# Arduino_Eth08d_MU-REV3.net
KiCad netlist of a schematic drawn in EAGLE
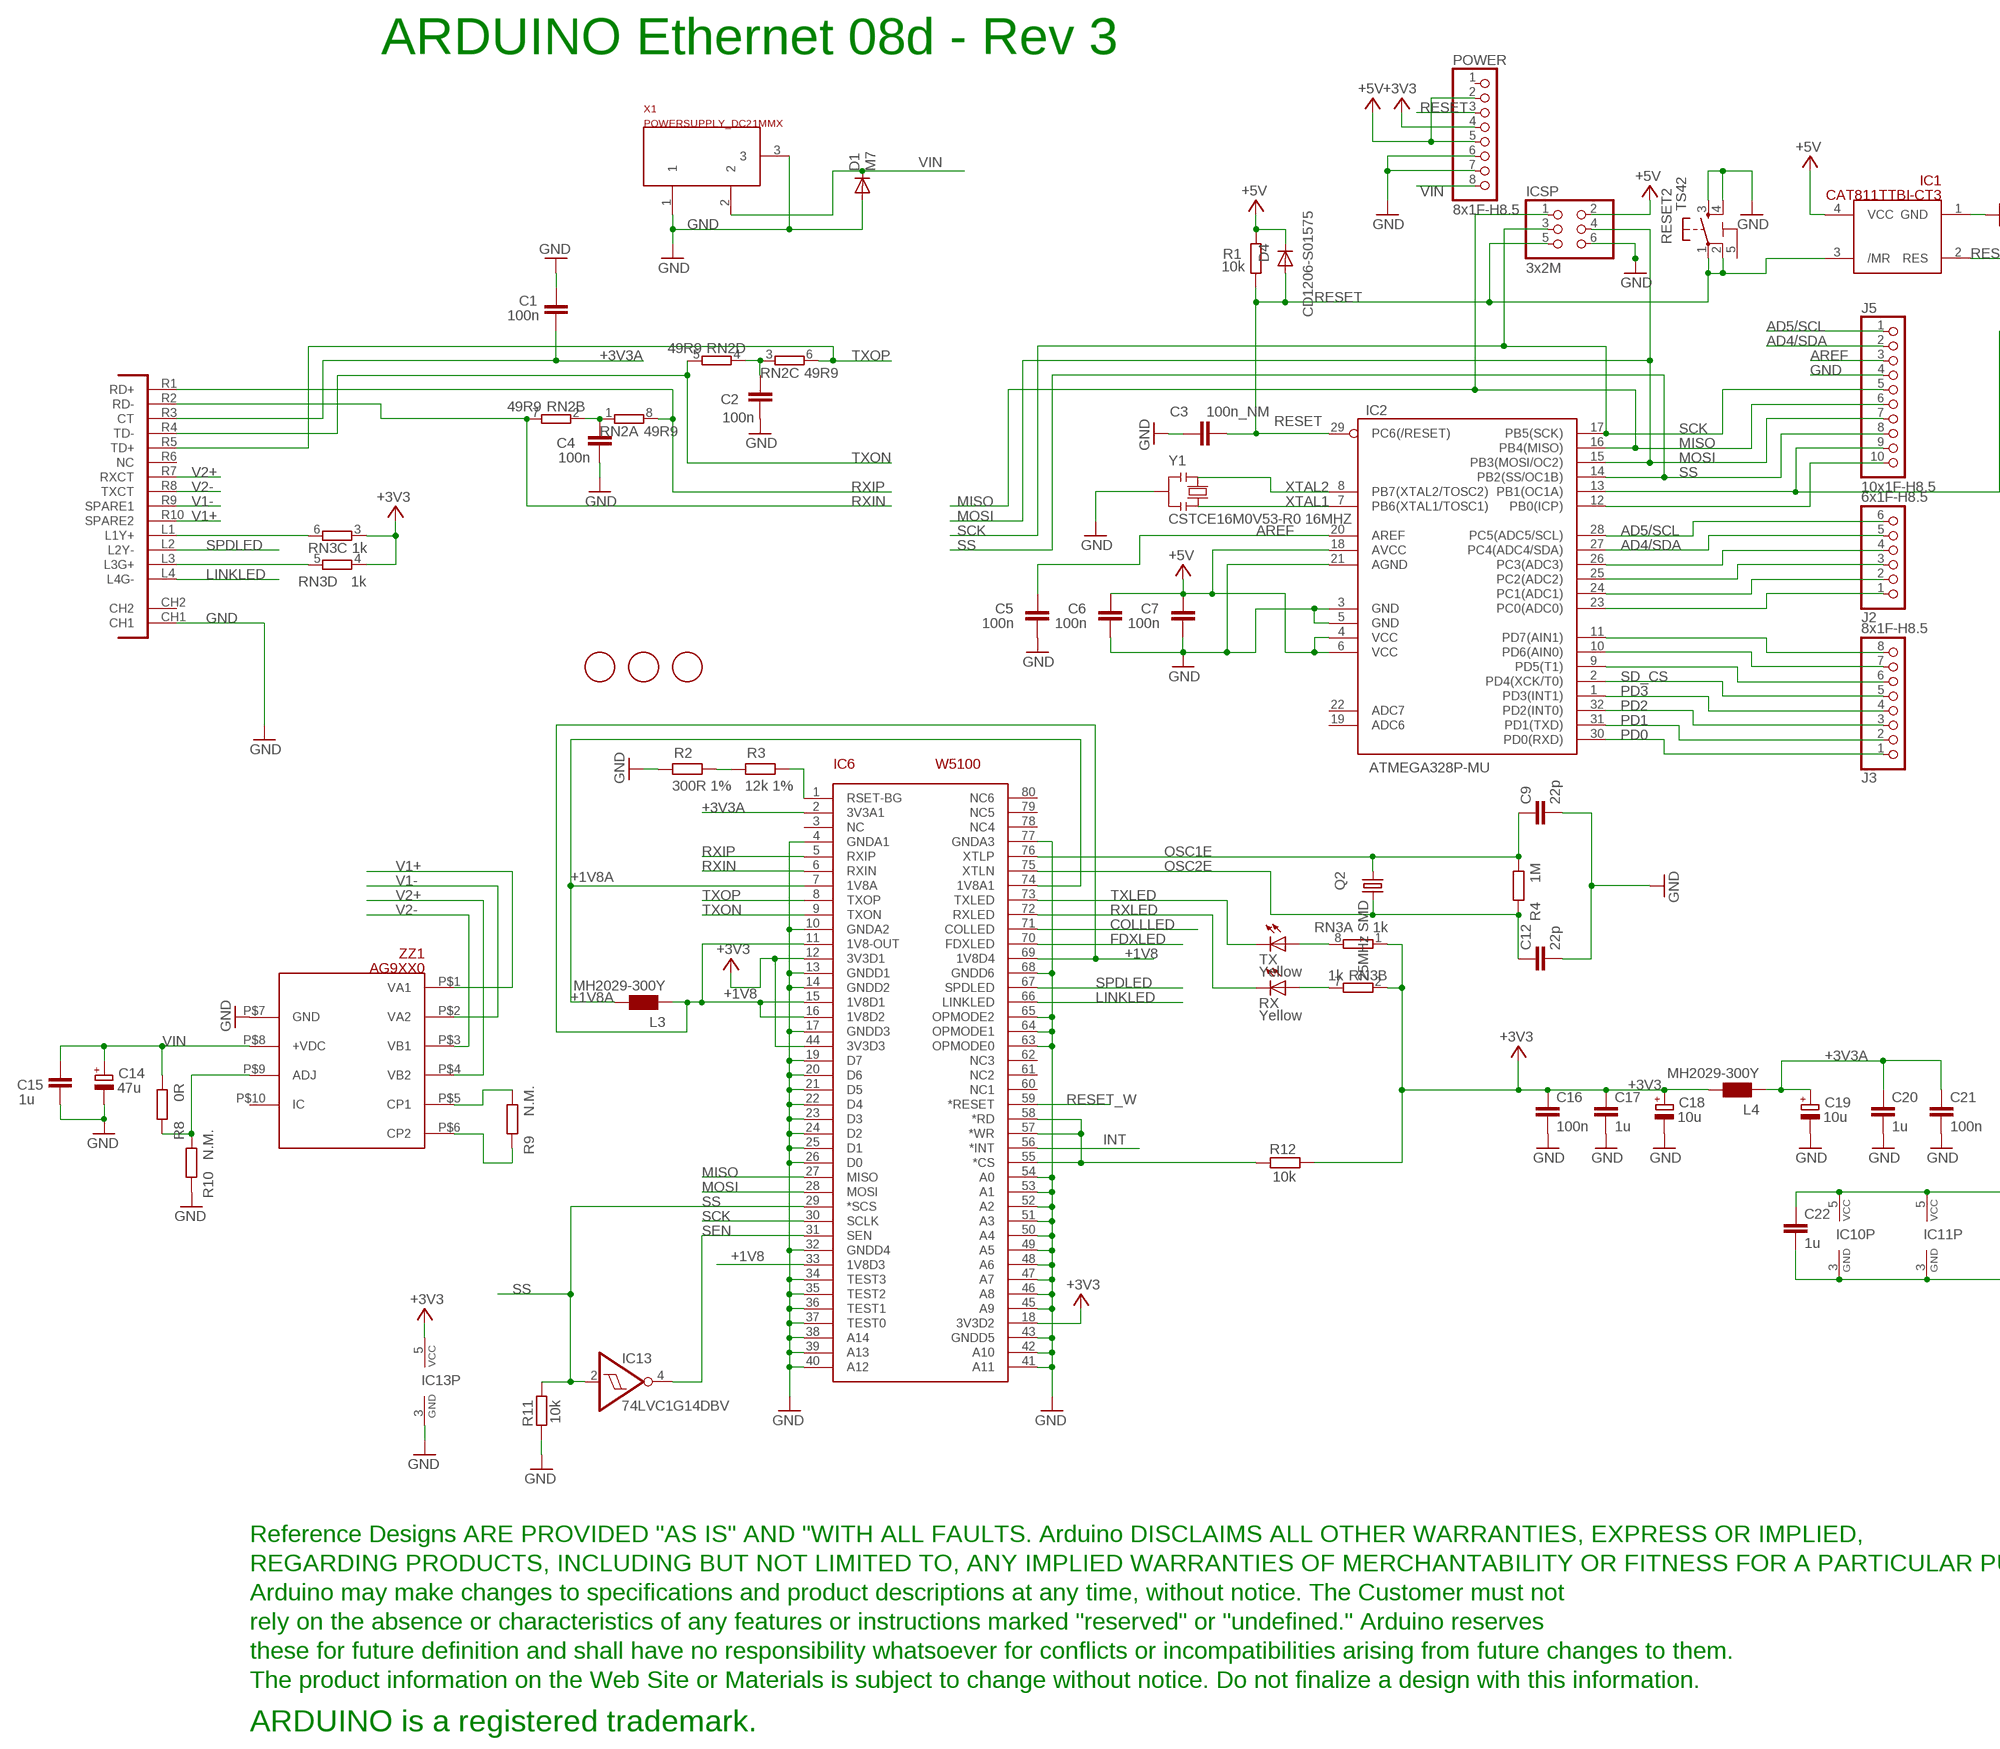
[diagram p0: schematic, sheet 1, part 1 of 2]
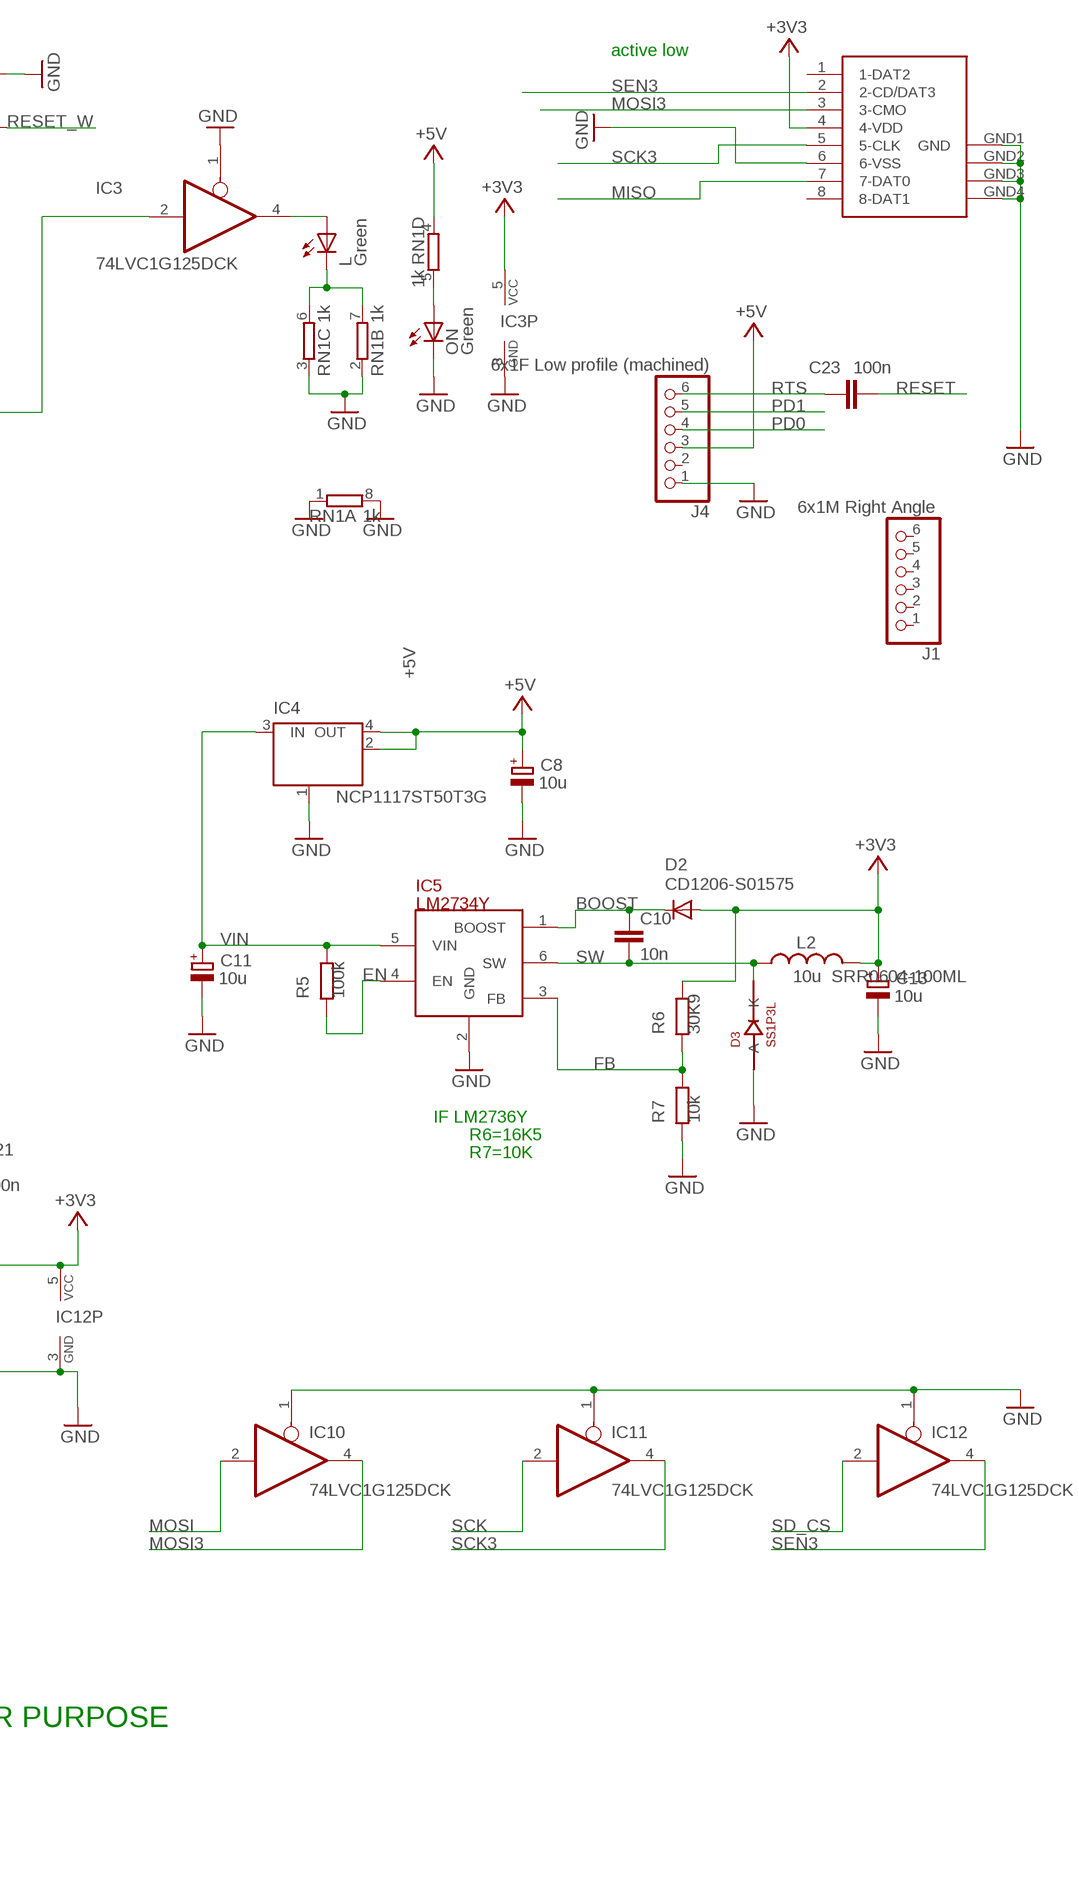
[diagram p1: schematic, sheet 1, part 2 of 2]

(export (version "E")
  (design (tool "Eeschema 10.0.6"))
  (components
    (comp (ref "C1")
      (value "100n")
      (footprint "eagle-import:C0603-ROUND")
      (libsource (lib "eagle-import") (part "C-EUC0603"))
    )
    (comp (ref "C2")
      (value "100n")
      (footprint "eagle-import:C0603-ROUND")
      (libsource (lib "eagle-import") (part "C-EUC0603"))
    )
    (comp (ref "C3")
      (value "100n_NM")
      (footprint "eagle-import:C0603-ROUND")
      (libsource (lib "eagle-import") (part "C-EUC0603"))
    )
    (comp (ref "C4")
      (value "100n")
      (footprint "eagle-import:C0603-ROUND")
      (libsource (lib "eagle-import") (part "C-EUC0603"))
    )
    (comp (ref "C5")
      (value "100n")
      (footprint "eagle-import:C0603-ROUND")
      (libsource (lib "eagle-import") (part "C-EUC0603"))
    )
    (comp (ref "C6")
      (value "100n")
      (footprint "eagle-import:C0603-ROUND")
      (libsource (lib "eagle-import") (part "C-EUC0603"))
    )
    (comp (ref "C7")
      (value "100n")
      (footprint "eagle-import:C0603-ROUND")
      (libsource (lib "eagle-import") (part "C-EUC0603"))
    )
    (comp (ref "C8")
      (value "10u")
      (footprint "eagle-import:SMC_B")
      (libsource (lib "eagle-import") (part "CPOL-EUSMCB"))
    )
    (comp (ref "C9")
      (value "22p")
      (footprint "eagle-import:C0603-ROUND")
      (libsource (lib "eagle-import") (part "C-EUC0603"))
    )
    (comp (ref "C10")
      (value "10n")
      (footprint "eagle-import:C0603-ROUND")
      (libsource (lib "eagle-import") (part "C-EUC0603"))
    )
    (comp (ref "C11")
      (value "10u")
      (footprint "eagle-import:SMC_B")
      (libsource (lib "eagle-import") (part "CPOL-EUSMCB"))
    )
    (comp (ref "C12")
      (value "22p")
      (footprint "eagle-import:C0603-ROUND")
      (libsource (lib "eagle-import") (part "C-EUC0603"))
    )
    (comp (ref "C13")
      (value "10u")
      (footprint "eagle-import:SMC_B")
      (libsource (lib "eagle-import") (part "CPOL-EUSMCB"))
    )
    (comp (ref "C14")
      (value "47u")
      (footprint "eagle-import:PANASONIC_D")
      (libsource (lib "eagle-import") (part "CPOL-EUD"))
    )
    (comp (ref "C15")
      (value "1u")
      (footprint "eagle-import:C0603-ROUND")
      (libsource (lib "eagle-import") (part "C-EUC0603"))
    )
    (comp (ref "C16")
      (value "100n")
      (footprint "eagle-import:C0603-ROUND")
      (libsource (lib "eagle-import") (part "C-EUC0603"))
    )
    (comp (ref "C17")
      (value "1u")
      (footprint "eagle-import:C0603-ROUND")
      (libsource (lib "eagle-import") (part "C-EUC0603"))
    )
    (comp (ref "C18")
      (value "10u")
      (footprint "eagle-import:SMC_B")
      (libsource (lib "eagle-import") (part "CPOL-EUSMCB"))
    )
    (comp (ref "C19")
      (value "10u")
      (footprint "eagle-import:SMC_B")
      (libsource (lib "eagle-import") (part "CPOL-EUSMCB"))
    )
    (comp (ref "C20")
      (value "1u")
      (footprint "eagle-import:C0603-ROUND")
      (libsource (lib "eagle-import") (part "C-EUC0603"))
    )
    (comp (ref "C21")
      (value "100n")
      (footprint "eagle-import:C0603-ROUND")
      (libsource (lib "eagle-import") (part "C-EUC0603"))
    )
    (comp (ref "C22")
      (value "1u")
      (footprint "eagle-import:C0603-ROUND")
      (libsource (lib "eagle-import") (part "C-EUC0603"))
    )
    (comp (ref "C23")
      (value "100n")
      (footprint "eagle-import:C0603-ROUND")
      (libsource (lib "eagle-import") (part "C-EUC0603"))
    )
    (comp (ref "D1")
      (value "M7")
      (footprint "eagle-import:SMB")
      (libsource (lib "eagle-import") (part "DIODE-SMB"))
    )
    (comp (ref "D2")
      (value "CD1206-S01575")
      (footprint "eagle-import:MINIMELF")
      (libsource (lib "eagle-import") (part "DIODE-MINIMELF"))
    )
    (comp (ref "D3")
      (value "SS1P3L")
      (footprint "eagle-import:DO220AAL")
      (libsource (lib "eagle-import") (part "SS1P3L"))
    )
    (comp (ref "D4")
      (value "CD1206-S01575")
      (footprint "eagle-import:MINIMELF")
      (libsource (lib "eagle-import") (part "DIODE-MINIMELF"))
    )
    (comp (ref "FD1")
      (value "FIDUCIALMOUNT")
      (footprint "eagle-import:FIDUCIA-MOUNT")
      (libsource (lib "eagle-import") (part "FIDUCIALMOUNT"))
    )
    (comp (ref "FD2")
      (value "FIDUCIALMOUNT")
      (footprint "eagle-import:FIDUCIA-MOUNT")
      (libsource (lib "eagle-import") (part "FIDUCIALMOUNT"))
    )
    (comp (ref "FD3")
      (value "FIDUCIALMOUNT")
      (footprint "eagle-import:FIDUCIA-MOUNT")
      (libsource (lib "eagle-import") (part "FIDUCIALMOUNT"))
    )
    (comp (ref "IC1")
      (value "CAT811TTBI-CT3")
      (footprint "eagle-import:SOT143")
      (libsource (lib "eagle-import") (part "STM812"))
    )
    (comp (ref "IC2")
      (value "ATMEGA328P-MU")
      (footprint "eagle-import:MLF32")
      (libsource (lib "eagle-import") (part "ATMEGAXX8-MUR"))
    )
    (comp (ref "IC3")
      (value "74LVC1G125DCK")
      (footprint "eagle-import:SC70-5")
      (libsource (lib "eagle-import") (part "741G125DCKLVC"))
    )
    (comp (ref "IC4")
      (value "NCP1117ST50T3G")
      (footprint "eagle-import:LINEAR_SOT223")
      (libsource (lib "eagle-import") (part "LINEAR_MC33269ST"))
    )
    (comp (ref "IC5")
      (value "LM2734Y")
      (footprint "eagle-import:SOT23-6")
      (libsource (lib "eagle-import") (part "LM2736Y"))
    )
    (comp (ref "IC6")
      (value "W5100")
      (footprint "eagle-import:SQFP-S-10X10-80")
      (libsource (lib "eagle-import") (part "W5100"))
    )
    (comp (ref "IC10")
      (value "74LVC1G125DCK")
      (footprint "eagle-import:SC70-5")
      (libsource (lib "eagle-import") (part "741G125DCKLVC"))
    )
    (comp (ref "IC11")
      (value "74LVC1G125DCK")
      (footprint "eagle-import:SC70-5")
      (libsource (lib "eagle-import") (part "741G125DCKLVC"))
    )
    (comp (ref "IC12")
      (value "74LVC1G125DCK")
      (footprint "eagle-import:SC70-5")
      (libsource (lib "eagle-import") (part "741G125DCKLVC"))
    )
    (comp (ref "IC13")
      (value "74LVC1G14DBV")
      (footprint "eagle-import:SOT23-5")
      (libsource (lib "eagle-import") (part "741G14DBVLVC"))
    )
    (comp (ref "ICSP")
      (value "3x2M")
      (footprint "eagle-import:2X03")
      (libsource (lib "eagle-import") (part "PINHD-2X3"))
    )
    (comp (ref "J1")
      (value "6x1M Right Angle")
      (footprint "eagle-import:1X06_90")
      (libsource (lib "eagle-import") (part "PINHD-1X6/90"))
    )
    (comp (ref "J2")
      (value "6x1F-H8.5")
      (footprint "eagle-import:1X06")
      (libsource (lib "eagle-import") (part "PINHD-1X6"))
    )
    (comp (ref "J3")
      (value "8x1F-H8.5")
      (footprint "eagle-import:1X08")
      (libsource (lib "eagle-import") (part "PINHD-1X8"))
    )
    (comp (ref "J4")
      (value "6x1F Low profile (machined)")
      (footprint "eagle-import:1X06-TH")
      (libsource (lib "eagle-import") (part "PINHD-1X6TH"))
    )
    (comp (ref "J5")
      (value "10x1F-H8.5")
      (footprint "eagle-import:1X10")
      (libsource (lib "eagle-import") (part "PINHD-1X10"))
    )
    (comp (ref "L")
      (value "Green")
      (footprint "eagle-import:CHIPLED_0805")
      (libsource (lib "eagle-import") (part "LEDCHIPLED_0805"))
    )
    (comp (ref "L2")
      (value "10u SRR0604-100ML")
      (footprint "eagle-import:SRR0604")
      (libsource (lib "eagle-import") (part "L-USSRR0604"))
    )
    (comp (ref "L3")
      (value "MH2029-300Y")
      (footprint "eagle-import:0805")
      (libsource (lib "eagle-import") (part "WE-CBF_0805"))
    )
    (comp (ref "L4")
      (value "MH2029-300Y")
      (footprint "eagle-import:0805")
      (libsource (lib "eagle-import") (part "WE-CBF_0805"))
    )
    (comp (ref "ON")
      (value "Green")
      (footprint "eagle-import:CHIPLED_0805")
      (libsource (lib "eagle-import") (part "LEDCHIPLED_0805"))
    )
    (comp (ref "POWER")
      (value "8x1F-H8.5")
      (footprint "eagle-import:1X08")
      (libsource (lib "eagle-import") (part "PINHD-1X8"))
    )
    (comp (ref "Q2")
      (value "25MHz SMD")
      (footprint "eagle-import:HC49UP")
      (libsource (lib "eagle-import") (part "CRYSTALHC49UP"))
    )
    (comp (ref "R1")
      (value "10k")
      (footprint "eagle-import:R0603-ROUND")
      (libsource (lib "eagle-import") (part "R-EU_0603-RND"))
    )
    (comp (ref "R2")
      (value "300R 1%")
      (footprint "eagle-import:R0603-ROUND")
      (libsource (lib "eagle-import") (part "R-EU_0603-RND"))
    )
    (comp (ref "R3")
      (value "12k 1%")
      (footprint "eagle-import:R0603-ROUND")
      (libsource (lib "eagle-import") (part "R-EU_0603-RND"))
    )
    (comp (ref "R4")
      (value "1M")
      (footprint "eagle-import:R0603-ROUND")
      (libsource (lib "eagle-import") (part "R-EU_0603-RND"))
    )
    (comp (ref "R5")
      (value "100k")
      (footprint "eagle-import:R0603-ROUND")
      (libsource (lib "eagle-import") (part "R-EU_0603-RND"))
    )
    (comp (ref "R6")
      (value "30K9")
      (footprint "eagle-import:R0603-ROUND")
      (libsource (lib "eagle-import") (part "R-EU_0603-RND"))
    )
    (comp (ref "R7")
      (value "10k")
      (footprint "eagle-import:R0603-ROUND")
      (libsource (lib "eagle-import") (part "R-EU_0603-RND"))
    )
    (comp (ref "R8")
      (value "0R")
      (footprint "eagle-import:R0603-ROUND")
      (libsource (lib "eagle-import") (part "R-EU_0603-RND"))
    )
    (comp (ref "R9")
      (value "N.M.")
      (footprint "eagle-import:R0603-ROUND")
      (libsource (lib "eagle-import") (part "R-EU_0603-RND"))
    )
    (comp (ref "R10")
      (value "N.M.")
      (footprint "eagle-import:R0603-ROUND")
      (libsource (lib "eagle-import") (part "R-EU_0603-RND"))
    )
    (comp (ref "R11")
      (value "10k")
      (footprint "eagle-import:R0603-ROUND")
      (libsource (lib "eagle-import") (part "R-EU_0603-RND"))
    )
    (comp (ref "R12")
      (value "10k")
      (footprint "eagle-import:R0603-ROUND")
      (libsource (lib "eagle-import") (part "R-EU_R0603"))
    )
    (comp (ref "RESET2")
      (value "TS42")
      (footprint "eagle-import:TS42")
      (libsource (lib "eagle-import") (part "TS42"))
    )
    (comp (ref "RN1")
      (value "1k")
      (footprint "eagle-import:CAY16")
      (libsource (lib "eagle-import") (part "4R-NCAY16"))
    )
    (comp (ref "RN2")
      (value "49R9")
      (footprint "eagle-import:CAY16")
      (libsource (lib "eagle-import") (part "4R-NCAY16"))
    )
    (comp (ref "RN3")
      (value "1k")
      (footprint "eagle-import:CAY16")
      (libsource (lib "eagle-import") (part "4R-NCAY16"))
    )
    (comp (ref "RX")
      (value "Yellow")
      (footprint "eagle-import:CHIPLED_0805")
      (libsource (lib "eagle-import") (part "LEDCHIPLED_0805"))
    )
    (comp (ref "TX")
      (value "Yellow")
      (footprint "eagle-import:CHIPLED_0805")
      (libsource (lib "eagle-import") (part "LEDCHIPLED_0805"))
    )
    (comp (ref "U$1")
      (value "POE-RJ45")
      (footprint "eagle-import:POE-RJ45")
      (libsource (lib "eagle-import") (part "POE-RJ45"))
    )
    (comp (ref "U$2")
      (value "DISCLAIMER")
      (footprint "eagle-import:DISCLAIMER")
      (libsource (lib "eagle-import") (part "DISCLAIMER"))
    )
    (comp (ref "X1")
      (value "POWERSUPPLY_DC21MMX")
      (footprint "eagle-import:POWERSUPPLY_DC-21MM")
      (libsource (lib "eagle-import") (part "POWERSUPPLY_DC21MMX"))
    )
    (comp (ref "X2")
      (value "SDCARD-15TW-8821")
      (footprint "eagle-import:SDCARD-15TW-8821")
      (libsource (lib "eagle-import") (part "SDCARD-15TW-8821"))
    )
    (comp (ref "Y1")
      (value "CSTCE16M0V53-R0 16MHZ")
      (footprint "eagle-import:RESONATOR")
      (libsource (lib "eagle-import") (part "RESONATORMU"))
    )
    (comp (ref "ZZ1")
      (value "AG9XX0")
      (footprint "eagle-import:AG9000")
      (libsource (lib "eagle-import") (part "AG9XX0"))
    )
  )
  (nets
    (net (code "1") (name "+3V3") (class "Default")
      (node (ref "C13") (pin "+") (pinfunction "+_+") (pintype "passive"))
      (node (ref "C16") (pin "1") (pinfunction "1_1") (pintype "passive"))
      (node (ref "C17") (pin "1") (pinfunction "1_1") (pintype "passive"))
      (node (ref "C18") (pin "+") (pinfunction "+_+") (pintype "passive"))
      (node (ref "C22") (pin "1") (pinfunction "1_1") (pintype "passive"))
      (node (ref "D2") (pin "A") (pinfunction "A_A") (pintype "passive"))
      (node (ref "IC10") (pin "5") (pinfunction "VCC_5") (pintype "power_in"))
      (node (ref "IC11") (pin "5") (pinfunction "VCC_5") (pintype "power_in"))
      (node (ref "IC12") (pin "5") (pinfunction "VCC_5") (pintype "power_in"))
      (node (ref "IC13") (pin "5") (pinfunction "VCC_5") (pintype "power_in"))
      (node (ref "IC3") (pin "5") (pinfunction "VCC_5") (pintype "power_in"))
      (node (ref "IC6") (pin "12") (pinfunction "3V3D1_12") (pintype "power_in"))
      (node (ref "IC6") (pin "18") (pinfunction "3V3D2_18") (pintype "power_in"))
      (node (ref "IC6") (pin "44") (pinfunction "3V3D3_44") (pintype "power_in"))
      (node (ref "L2") (pin "P$2") (pinfunction "2_P$2") (pintype "passive"))
      (node (ref "L4") (pin "2") (pinfunction "2_2") (pintype "passive"))
      (node (ref "POWER") (pin "4") (pinfunction "4_4") (pintype "passive"))
      (node (ref "R12") (pin "2") (pinfunction "2_2") (pintype "passive"))
      (node (ref "R6") (pin "1") (pinfunction "1_1") (pintype "passive"))
      (node (ref "RN3") (pin "1") (pinfunction "1_1") (pintype "passive"))
      (node (ref "RN3") (pin "2") (pinfunction "1_2") (pintype "passive"))
      (node (ref "RN3") (pin "3") (pinfunction "1_3") (pintype "passive"))
      (node (ref "RN3") (pin "4") (pinfunction "1_4") (pintype "passive"))
      (node (ref "X2") (pin "4") (pinfunction "4-VDD_4") (pintype "bidirectional"))
    )
    (net (code "2") (name "+5V") (class "Default")
      (node (ref "C6") (pin "1") (pinfunction "1_1") (pintype "passive"))
      (node (ref "C7") (pin "1") (pinfunction "1_1") (pintype "passive"))
      (node (ref "C8") (pin "+") (pinfunction "+_+") (pintype "passive"))
      (node (ref "D4") (pin "C") (pinfunction "C_C") (pintype "passive"))
      (node (ref "IC1") (pin "4") (pinfunction "VCC_4") (pintype "power_in"))
      (node (ref "IC2") (pin "18") (pinfunction "AVCC_18") (pintype "bidirectional"))
      (node (ref "IC2") (pin "4") (pinfunction "VCC_4") (pintype "bidirectional"))
      (node (ref "IC2") (pin "6") (pinfunction "VCC_6") (pintype "bidirectional"))
      (node (ref "IC4") (pin "2") (pinfunction "OUT_2") (pintype "passive"))
      (node (ref "IC4") (pin "4") (pinfunction "OUT_4") (pintype "passive"))
      (node (ref "ICSP") (pin "2") (pinfunction "2_2") (pintype "passive"))
      (node (ref "J4") (pin "3") (pinfunction "3_3") (pintype "passive"))
      (node (ref "POWER") (pin "2") (pinfunction "2_2") (pintype "passive"))
      (node (ref "POWER") (pin "5") (pinfunction "5_5") (pintype "passive"))
      (node (ref "R1") (pin "2") (pinfunction "2_2") (pintype "passive"))
      (node (ref "RN1") (pin "4") (pinfunction "1_4") (pintype "passive"))
    )
    (net (code "3") (name "/+1V8") (class "Default")
      (node (ref "IC6") (pin "11") (pinfunction "1V8-OUT_11") (pintype "power_in"))
      (node (ref "IC6") (pin "15") (pinfunction "1V8D1_15") (pintype "power_in"))
      (node (ref "IC6") (pin "16") (pinfunction "1V8D2_16") (pintype "power_in"))
      (node (ref "IC6") (pin "33") (pinfunction "1V8D3_33") (pintype "power_in"))
      (node (ref "IC6") (pin "69") (pinfunction "1V8D4_69") (pintype "power_in"))
      (node (ref "L3") (pin "1") (pinfunction "1_1") (pintype "passive"))
    )
    (net (code "4") (name "/+1V8A") (class "Default")
      (node (ref "IC6") (pin "7") (pinfunction "1V8A_7") (pintype "power_in"))
      (node (ref "IC6") (pin "74") (pinfunction "1V8A1_74") (pintype "power_in"))
      (node (ref "L3") (pin "2") (pinfunction "2_2") (pintype "passive"))
    )
    (net (code "5") (name "/+3V3A") (class "Default")
      (node (ref "C1") (pin "1") (pinfunction "1_1") (pintype "passive"))
      (node (ref "C19") (pin "+") (pinfunction "+_+") (pintype "passive"))
      (node (ref "C20") (pin "1") (pinfunction "1_1") (pintype "passive"))
      (node (ref "C21") (pin "1") (pinfunction "1_1") (pintype "passive"))
      (node (ref "IC6") (pin "2") (pinfunction "3V3A1_2") (pintype "power_in"))
      (node (ref "L4") (pin "1") (pinfunction "1_1") (pintype "passive"))
      (node (ref "U$1") (pin "R3") (pinfunction "CT_R3") (pintype "bidirectional"))
    )
    (net (code "6") (name "/5-GND") (class "Default")
      (node (ref "RESET2") (pin "5") (pinfunction "5-GND_5") (pintype "power_in"))
    )
    (net (code "7") (name "/AD4{slash}SDA") (class "Default")
      (node (ref "IC2") (pin "27") (pinfunction "PC4(ADC4/SDA)_27") (pintype "bidirectional"))
      (node (ref "J2") (pin "5") (pinfunction "5_5") (pintype "passive"))
      (node (ref "J5") (pin "2") (pinfunction "2_2") (pintype "passive"))
    )
    (net (code "8") (name "/AD5{slash}SCL") (class "Default")
      (node (ref "IC2") (pin "28") (pinfunction "PC5(ADC5/SCL)_28") (pintype "bidirectional"))
      (node (ref "J2") (pin "6") (pinfunction "6_6") (pintype "passive"))
      (node (ref "J5") (pin "1") (pinfunction "1_1") (pintype "passive"))
    )
    (net (code "9") (name "/AREF") (class "Default")
      (node (ref "C5") (pin "1") (pinfunction "1_1") (pintype "passive"))
      (node (ref "IC2") (pin "20") (pinfunction "AREF_20") (pintype "bidirectional"))
      (node (ref "J5") (pin "3") (pinfunction "3_3") (pintype "passive"))
    )
    (net (code "10") (name "/BOOST") (class "Default")
      (node (ref "C10") (pin "1") (pinfunction "1_1") (pintype "passive"))
      (node (ref "D2") (pin "C") (pinfunction "C_C") (pintype "passive"))
      (node (ref "IC5") (pin "1") (pinfunction "BOOST_1") (pintype "input"))
    )
    (net (code "11") (name "/COLLLED") (class "Default")
      (node (ref "IC6") (pin "71") (pinfunction "COLLED_71") (pintype "output"))
    )
    (net (code "12") (name "/EN") (class "Default")
      (node (ref "IC5") (pin "4") (pinfunction "EN_4") (pintype "input"))
      (node (ref "R5") (pin "2") (pinfunction "2_2") (pintype "passive"))
    )
    (net (code "13") (name "/FB") (class "Default")
      (node (ref "IC5") (pin "3") (pinfunction "FB_3") (pintype "input"))
      (node (ref "R6") (pin "2") (pinfunction "2_2") (pintype "passive"))
      (node (ref "R7") (pin "1") (pinfunction "1_1") (pintype "passive"))
    )
    (net (code "14") (name "/FDXLED") (class "Default")
      (node (ref "IC6") (pin "70") (pinfunction "FDXLED_70") (pintype "output"))
    )
    (net (code "15") (name "/INT") (class "Default")
      (node (ref "IC6") (pin "56") (pinfunction "*INT_56") (pintype "input"))
    )
    (net (code "16") (name "/LINKLED") (class "Default")
      (node (ref "IC6") (pin "66") (pinfunction "LINKLED_66") (pintype "output"))
      (node (ref "U$1") (pin "L4") (pinfunction "L4G-_L4") (pintype "bidirectional"))
    )
    (net (code "17") (name "/MISO") (class "Default")
      (node (ref "IC2") (pin "16") (pinfunction "PB4(MISO)_16") (pintype "bidirectional"))
      (node (ref "IC6") (pin "27") (pinfunction "MISO_27") (pintype "input"))
      (node (ref "ICSP") (pin "1") (pinfunction "1_1") (pintype "passive"))
      (node (ref "J5") (pin "6") (pinfunction "6_6") (pintype "passive"))
      (node (ref "X2") (pin "7") (pinfunction "7-DAT0_7") (pintype "bidirectional"))
    )
    (net (code "18") (name "/MOSI") (class "Default")
      (node (ref "IC10") (pin "2") (pinfunction "I_2") (pintype "input"))
      (node (ref "IC2") (pin "15") (pinfunction "PB3(MOSI/OC2)_15") (pintype "bidirectional"))
      (node (ref "IC6") (pin "28") (pinfunction "MOSI_28") (pintype "output"))
      (node (ref "ICSP") (pin "4") (pinfunction "4_4") (pintype "passive"))
      (node (ref "J5") (pin "7") (pinfunction "7_7") (pintype "passive"))
    )
    (net (code "19") (name "/MOSI3") (class "Default")
      (node (ref "IC10") (pin "4") (pinfunction "O_4") (pintype "tri_state"))
      (node (ref "X2") (pin "3") (pinfunction "3-CMO_3") (pintype "bidirectional"))
    )
    (net (code "20") (name "/OSC1E") (class "Default")
      (node (ref "C9") (pin "1") (pinfunction "1_1") (pintype "passive"))
      (node (ref "IC6") (pin "76") (pinfunction "XTLP_76") (pintype "output"))
      (node (ref "Q2") (pin "1") (pinfunction "1_1") (pintype "passive"))
      (node (ref "R4") (pin "1") (pinfunction "1_1") (pintype "passive"))
    )
    (net (code "21") (name "/OSC2E") (class "Default")
      (node (ref "C12") (pin "1") (pinfunction "1_1") (pintype "passive"))
      (node (ref "IC6") (pin "75") (pinfunction "XTLN_75") (pintype "output"))
      (node (ref "Q2") (pin "2") (pinfunction "2_2") (pintype "passive"))
      (node (ref "R4") (pin "2") (pinfunction "2_2") (pintype "passive"))
    )
    (net (code "22") (name "/PD0") (class "Default")
      (node (ref "IC2") (pin "30") (pinfunction "PD0(RXD)_30") (pintype "bidirectional"))
      (node (ref "J3") (pin "1") (pinfunction "1_1") (pintype "passive"))
      (node (ref "J4") (pin "4") (pinfunction "4_4") (pintype "passive"))
    )
    (net (code "23") (name "/PD1") (class "Default")
      (node (ref "IC2") (pin "31") (pinfunction "PD1(TXD)_31") (pintype "bidirectional"))
      (node (ref "J3") (pin "2") (pinfunction "2_2") (pintype "passive"))
      (node (ref "J4") (pin "5") (pinfunction "5_5") (pintype "passive"))
    )
    (net (code "24") (name "/PD2") (class "Default")
      (node (ref "IC2") (pin "32") (pinfunction "PD2(INT0)_32") (pintype "bidirectional"))
      (node (ref "J3") (pin "3") (pinfunction "3_3") (pintype "passive"))
    )
    (net (code "25") (name "/PD3") (class "Default")
      (node (ref "IC2") (pin "1") (pinfunction "PD3(INT1)_1") (pintype "bidirectional"))
      (node (ref "J3") (pin "4") (pinfunction "4_4") (pintype "passive"))
    )
    (net (code "26") (name "/RESET") (class "Default")
      (node (ref "C23") (pin "1") (pinfunction "1_1") (pintype "passive"))
      (node (ref "C3") (pin "1") (pinfunction "1_1") (pintype "passive"))
      (node (ref "D4") (pin "A") (pinfunction "A_A") (pintype "passive"))
      (node (ref "IC1") (pin "3") (pinfunction "/MR_3") (pintype "input"))
      (node (ref "IC2") (pin "29") (pinfunction "PC6(/RESET)_29") (pintype "bidirectional"))
      (node (ref "ICSP") (pin "5") (pinfunction "5_5") (pintype "passive"))
      (node (ref "POWER") (pin "3") (pinfunction "3_3") (pintype "passive"))
      (node (ref "R1") (pin "1") (pinfunction "1_1") (pintype "passive"))
      (node (ref "RESET2") (pin "1") (pinfunction "1_1") (pintype "passive"))
      (node (ref "RESET2") (pin "2") (pinfunction "2_2") (pintype "passive"))
    )
    (net (code "27") (name "/RESET_W") (class "Default")
      (node (ref "IC1") (pin "2") (pinfunction "RES_2") (pintype "output"))
      (node (ref "IC6") (pin "59") (pinfunction "*RESET_59") (pintype "input"))
    )
    (net (code "28") (name "/RTS") (class "Default")
      (node (ref "C23") (pin "2") (pinfunction "2_2") (pintype "passive"))
      (node (ref "J4") (pin "6") (pinfunction "6_6") (pintype "passive"))
    )
    (net (code "29") (name "/RXIN") (class "Default")
      (node (ref "IC6") (pin "6") (pinfunction "RXIN_6") (pintype "input"))
      (node (ref "RN2") (pin "7") (pinfunction "2_7") (pintype "passive"))
      (node (ref "U$1") (pin "R2") (pinfunction "RD-_R2") (pintype "bidirectional"))
    )
    (net (code "30") (name "/RXIP") (class "Default")
      (node (ref "IC6") (pin "5") (pinfunction "RXIP_5") (pintype "input"))
      (node (ref "RN2") (pin "8") (pinfunction "2_8") (pintype "passive"))
      (node (ref "U$1") (pin "R1") (pinfunction "RD+_R1") (pintype "bidirectional"))
    )
    (net (code "31") (name "/RXLED") (class "Default")
      (node (ref "IC6") (pin "72") (pinfunction "RXLED_72") (pintype "output"))
      (node (ref "RX") (pin "C") (pinfunction "C_C") (pintype "passive"))
    )
    (net (code "32") (name "/SCK") (class "Default")
      (node (ref "IC11") (pin "2") (pinfunction "I_2") (pintype "input"))
      (node (ref "IC2") (pin "17") (pinfunction "PB5(SCK)_17") (pintype "bidirectional"))
      (node (ref "IC6") (pin "30") (pinfunction "SCLK_30") (pintype "input"))
      (node (ref "ICSP") (pin "3") (pinfunction "3_3") (pintype "passive"))
      (node (ref "J5") (pin "5") (pinfunction "5_5") (pintype "passive"))
    )
    (net (code "33") (name "/SCK3") (class "Default")
      (node (ref "IC11") (pin "4") (pinfunction "O_4") (pintype "tri_state"))
      (node (ref "X2") (pin "5") (pinfunction "5-CLK_5") (pintype "bidirectional"))
    )
    (net (code "34") (name "/SD_CS") (class "Default")
      (node (ref "IC12") (pin "2") (pinfunction "I_2") (pintype "input"))
      (node (ref "IC2") (pin "2") (pinfunction "PD4(XCK/T0)_2") (pintype "bidirectional"))
      (node (ref "J3") (pin "5") (pinfunction "5_5") (pintype "passive"))
    )
    (net (code "35") (name "/SEN") (class "Default")
      (node (ref "IC13") (pin "4") (pinfunction "O_4") (pintype "output"))
      (node (ref "IC6") (pin "31") (pinfunction "SEN_31") (pintype "input"))
    )
    (net (code "36") (name "/SEN3") (class "Default")
      (node (ref "IC12") (pin "4") (pinfunction "O_4") (pintype "tri_state"))
      (node (ref "X2") (pin "2") (pinfunction "2-CD/DAT3_2") (pintype "bidirectional"))
    )
    (net (code "37") (name "/SPDLED") (class "Default")
      (node (ref "IC6") (pin "67") (pinfunction "SPDLED_67") (pintype "output"))
      (node (ref "U$1") (pin "L2") (pinfunction "L2Y-_L2") (pintype "bidirectional"))
    )
    (net (code "38") (name "/SS") (class "Default")
      (node (ref "IC13") (pin "2") (pinfunction "I_2") (pintype "input"))
      (node (ref "IC2") (pin "14") (pinfunction "PB2(SS/OC1B)_14") (pintype "bidirectional"))
      (node (ref "IC6") (pin "29") (pinfunction "*SCS_29") (pintype "input"))
      (node (ref "J5") (pin "8") (pinfunction "8_8") (pintype "passive"))
      (node (ref "R11") (pin "2") (pinfunction "2_2") (pintype "passive"))
    )
    (net (code "39") (name "/SW") (class "Default")
      (node (ref "C10") (pin "2") (pinfunction "2_2") (pintype "passive"))
      (node (ref "D3") (pin "P$1") (pinfunction "K_P$1") (pintype "bidirectional"))
      (node (ref "IC5") (pin "6") (pinfunction "SW_6") (pintype "output"))
      (node (ref "L2") (pin "P$1") (pinfunction "1_P$1") (pintype "passive"))
    )
    (net (code "40") (name "/TXLED") (class "Default")
      (node (ref "IC6") (pin "73") (pinfunction "TXLED_73") (pintype "output"))
      (node (ref "TX") (pin "C") (pinfunction "C_C") (pintype "passive"))
    )
    (net (code "41") (name "/TXON") (class "Default")
      (node (ref "IC6") (pin "9") (pinfunction "TXON_9") (pintype "output"))
      (node (ref "RN2") (pin "5") (pinfunction "2_5") (pintype "passive"))
      (node (ref "U$1") (pin "R4") (pinfunction "TD-_R4") (pintype "bidirectional"))
    )
    (net (code "42") (name "/TXOP") (class "Default")
      (node (ref "IC6") (pin "8") (pinfunction "TXOP_8") (pintype "output"))
      (node (ref "RN2") (pin "6") (pinfunction "2_6") (pintype "passive"))
      (node (ref "U$1") (pin "R5") (pinfunction "TD+_R5") (pintype "bidirectional"))
    )
    (net (code "43") (name "/V1+") (class "Default")
      (node (ref "U$1") (pin "R10") (pinfunction "SPARE2_R10") (pintype "bidirectional"))
      (node (ref "ZZ1") (pin "P$1") (pinfunction "VA1_P$1") (pintype "input"))
    )
    (net (code "44") (name "/V1-") (class "Default")
      (node (ref "U$1") (pin "R9") (pinfunction "SPARE1_R9") (pintype "bidirectional"))
      (node (ref "ZZ1") (pin "P$2") (pinfunction "VA2_P$2") (pintype "input"))
    )
    (net (code "45") (name "/V2+") (class "Default")
      (node (ref "U$1") (pin "R7") (pinfunction "RXCT_R7") (pintype "bidirectional"))
      (node (ref "ZZ1") (pin "P$4") (pinfunction "VB2_P$4") (pintype "input"))
    )
    (net (code "46") (name "/V2-") (class "Default")
      (node (ref "U$1") (pin "R8") (pinfunction "TXCT_R8") (pintype "bidirectional"))
      (node (ref "ZZ1") (pin "P$3") (pinfunction "VB1_P$3") (pintype "input"))
    )
    (net (code "47") (name "/VIN") (class "Default")
      (node (ref "C11") (pin "+") (pinfunction "+_+") (pintype "passive"))
      (node (ref "C14") (pin "+") (pinfunction "+_+") (pintype "passive"))
      (node (ref "C15") (pin "2") (pinfunction "2_2") (pintype "passive"))
      (node (ref "D1") (pin "C") (pinfunction "C_C") (pintype "passive"))
      (node (ref "IC4") (pin "3") (pinfunction "IN_3") (pintype "input"))
      (node (ref "IC5") (pin "5") (pinfunction "VIN_5") (pintype "input"))
      (node (ref "POWER") (pin "8") (pinfunction "8_8") (pintype "passive"))
      (node (ref "R5") (pin "1") (pinfunction "1_1") (pintype "passive"))
      (node (ref "R8") (pin "1") (pinfunction "1_1") (pintype "passive"))
      (node (ref "X1") (pin "2") (pinfunction "2_2") (pintype "power_in"))
      (node (ref "ZZ1") (pin "P$8") (pinfunction "+VDC_P$8") (pintype "power_in"))
    )
    (net (code "48") (name "/XTAL1") (class "Default")
      (node (ref "IC2") (pin "7") (pinfunction "PB6(XTAL1/TOSC1)_7") (pintype "bidirectional"))
      (node (ref "Y1") (pin "3") (pinfunction "3_3") (pintype "passive"))
    )
    (net (code "49") (name "/XTAL2") (class "Default")
      (node (ref "IC2") (pin "8") (pinfunction "PB7(XTAL2/TOSC2)_8") (pintype "bidirectional"))
      (node (ref "Y1") (pin "1") (pinfunction "1_1") (pintype "passive"))
    )
    (net (code "50") (name "GND") (class "Default")
      (node (ref "C1") (pin "2") (pinfunction "2_2") (pintype "passive"))
      (node (ref "C11") (pin "-") (pinfunction "-_-") (pintype "passive"))
      (node (ref "C12") (pin "2") (pinfunction "2_2") (pintype "passive"))
      (node (ref "C13") (pin "-") (pinfunction "-_-") (pintype "passive"))
      (node (ref "C14") (pin "-") (pinfunction "-_-") (pintype "passive"))
      (node (ref "C15") (pin "1") (pinfunction "1_1") (pintype "passive"))
      (node (ref "C16") (pin "2") (pinfunction "2_2") (pintype "passive"))
      (node (ref "C17") (pin "2") (pinfunction "2_2") (pintype "passive"))
      (node (ref "C18") (pin "-") (pinfunction "-_-") (pintype "passive"))
      (node (ref "C19") (pin "-") (pinfunction "-_-") (pintype "passive"))
      (node (ref "C2") (pin "1") (pinfunction "1_1") (pintype "passive"))
      (node (ref "C20") (pin "2") (pinfunction "2_2") (pintype "passive"))
      (node (ref "C21") (pin "2") (pinfunction "2_2") (pintype "passive"))
      (node (ref "C22") (pin "2") (pinfunction "2_2") (pintype "passive"))
      (node (ref "C3") (pin "2") (pinfunction "2_2") (pintype "passive"))
      (node (ref "C4") (pin "1") (pinfunction "1_1") (pintype "passive"))
      (node (ref "C5") (pin "2") (pinfunction "2_2") (pintype "passive"))
      (node (ref "C6") (pin "2") (pinfunction "2_2") (pintype "passive"))
      (node (ref "C7") (pin "2") (pinfunction "2_2") (pintype "passive"))
      (node (ref "C8") (pin "-") (pinfunction "-_-") (pintype "passive"))
      (node (ref "C9") (pin "2") (pinfunction "2_2") (pintype "passive"))
      (node (ref "D1") (pin "A") (pinfunction "A_A") (pintype "passive"))
      (node (ref "D3") (pin "P$2") (pinfunction "A_P$2") (pintype "bidirectional"))
      (node (ref "IC1") (pin "1") (pinfunction "GND_1") (pintype "power_in"))
      (node (ref "IC10") (pin "1") (pinfunction "OE_1") (pintype "input"))
      (node (ref "IC10") (pin "3") (pinfunction "GND_3") (pintype "power_in"))
      (node (ref "IC11") (pin "1") (pinfunction "OE_1") (pintype "input"))
      (node (ref "IC11") (pin "3") (pinfunction "GND_3") (pintype "power_in"))
      (node (ref "IC12") (pin "1") (pinfunction "OE_1") (pintype "input"))
      (node (ref "IC12") (pin "3") (pinfunction "GND_3") (pintype "power_in"))
      (node (ref "IC13") (pin "3") (pinfunction "GND_3") (pintype "power_in"))
      (node (ref "IC2") (pin "21") (pinfunction "AGND_21") (pintype "bidirectional"))
      (node (ref "IC2") (pin "3") (pinfunction "GND_3") (pintype "bidirectional"))
      (node (ref "IC2") (pin "5") (pinfunction "GND_5") (pintype "bidirectional"))
      (node (ref "IC3") (pin "1") (pinfunction "OE_1") (pintype "input"))
      (node (ref "IC3") (pin "3") (pinfunction "GND_3") (pintype "power_in"))
      (node (ref "IC4") (pin "1") (pinfunction "GND/ADJ_1") (pintype "input"))
      (node (ref "IC5") (pin "2") (pinfunction "GND_2") (pintype "power_in"))
      (node (ref "IC6") (pin "10") (pinfunction "GNDA2_10") (pintype "power_in"))
      (node (ref "IC6") (pin "13") (pinfunction "GNDD1_13") (pintype "power_in"))
      (node (ref "IC6") (pin "14") (pinfunction "GNDD2_14") (pintype "power_in"))
      (node (ref "IC6") (pin "17") (pinfunction "GNDD3_17") (pintype "power_in"))
      (node (ref "IC6") (pin "19") (pinfunction "D7_19") (pintype "input"))
      (node (ref "IC6") (pin "20") (pinfunction "D6_20") (pintype "input"))
      (node (ref "IC6") (pin "21") (pinfunction "D5_21") (pintype "input"))
      (node (ref "IC6") (pin "22") (pinfunction "D4_22") (pintype "input"))
      (node (ref "IC6") (pin "23") (pinfunction "D3_23") (pintype "input"))
      (node (ref "IC6") (pin "24") (pinfunction "D2_24") (pintype "input"))
      (node (ref "IC6") (pin "25") (pinfunction "D1_25") (pintype "input"))
      (node (ref "IC6") (pin "26") (pinfunction "D0_26") (pintype "input"))
      (node (ref "IC6") (pin "32") (pinfunction "GNDD4_32") (pintype "power_in"))
      (node (ref "IC6") (pin "34") (pinfunction "TEST3_34") (pintype "input"))
      (node (ref "IC6") (pin "35") (pinfunction "TEST2_35") (pintype "input"))
      (node (ref "IC6") (pin "36") (pinfunction "TEST1_36") (pintype "input"))
      (node (ref "IC6") (pin "37") (pinfunction "TEST0_37") (pintype "input"))
      (node (ref "IC6") (pin "38") (pinfunction "A14_38") (pintype "input"))
      (node (ref "IC6") (pin "39") (pinfunction "A13_39") (pintype "input"))
      (node (ref "IC6") (pin "4") (pinfunction "GNDA1_4") (pintype "power_in"))
      (node (ref "IC6") (pin "40") (pinfunction "A12_40") (pintype "input"))
      (node (ref "IC6") (pin "41") (pinfunction "A11_41") (pintype "input"))
      (node (ref "IC6") (pin "42") (pinfunction "A10_42") (pintype "input"))
      (node (ref "IC6") (pin "43") (pinfunction "GNDD5_43") (pintype "power_in"))
      (node (ref "IC6") (pin "45") (pinfunction "A9_45") (pintype "input"))
      (node (ref "IC6") (pin "46") (pinfunction "A8_46") (pintype "input"))
      (node (ref "IC6") (pin "47") (pinfunction "A7_47") (pintype "input"))
      (node (ref "IC6") (pin "48") (pinfunction "A6_48") (pintype "input"))
      (node (ref "IC6") (pin "49") (pinfunction "A5_49") (pintype "input"))
      (node (ref "IC6") (pin "50") (pinfunction "A4_50") (pintype "input"))
      (node (ref "IC6") (pin "51") (pinfunction "A3_51") (pintype "input"))
      (node (ref "IC6") (pin "52") (pinfunction "A2_52") (pintype "input"))
      (node (ref "IC6") (pin "53") (pinfunction "A1_53") (pintype "input"))
      (node (ref "IC6") (pin "54") (pinfunction "A0_54") (pintype "input"))
      (node (ref "IC6") (pin "63") (pinfunction "OPMODE0_63") (pintype "input"))
      (node (ref "IC6") (pin "64") (pinfunction "OPMODE1_64") (pintype "input"))
      (node (ref "IC6") (pin "65") (pinfunction "OPMODE2_65") (pintype "input"))
      (node (ref "IC6") (pin "68") (pinfunction "GNDD6_68") (pintype "power_in"))
      (node (ref "IC6") (pin "77") (pinfunction "GNDA3_77") (pintype "power_in"))
      (node (ref "ICSP") (pin "6") (pinfunction "6_6") (pintype "passive"))
      (node (ref "J4") (pin "1") (pinfunction "1_1") (pintype "passive"))
      (node (ref "J5") (pin "4") (pinfunction "4_4") (pintype "passive"))
      (node (ref "ON") (pin "C") (pinfunction "C_C") (pintype "passive"))
      (node (ref "POWER") (pin "6") (pinfunction "6_6") (pintype "passive"))
      (node (ref "POWER") (pin "7") (pinfunction "7_7") (pintype "passive"))
      (node (ref "R10") (pin "2") (pinfunction "2_2") (pintype "passive"))
      (node (ref "R11") (pin "1") (pinfunction "1_1") (pintype "passive"))
      (node (ref "R2") (pin "2") (pinfunction "2_2") (pintype "passive"))
      (node (ref "R7") (pin "2") (pinfunction "2_2") (pintype "passive"))
      (node (ref "RESET2") (pin "3") (pinfunction "3_3") (pintype "passive"))
      (node (ref "RESET2") (pin "4") (pinfunction "4_4") (pintype "passive"))
      (node (ref "RN1") (pin "1") (pinfunction "1_1") (pintype "passive"))
      (node (ref "RN1") (pin "2") (pinfunction "1_2") (pintype "passive"))
      (node (ref "RN1") (pin "3") (pinfunction "1_3") (pintype "passive"))
      (node (ref "RN1") (pin "8") (pinfunction "2_8") (pintype "passive"))
      (node (ref "U$1") (pin "CH1") (pinfunction "CH1_CH1") (pintype "bidirectional"))
      (node (ref "X1") (pin "1") (pinfunction "1_1") (pintype "power_in"))
      (node (ref "X1") (pin "3") (pinfunction "3_3") (pintype "power_in"))
      (node (ref "X2") (pin "6") (pinfunction "6-VSS_6") (pintype "bidirectional"))
      (node (ref "X2") (pin "GND1") (pinfunction "GND_GND1") (pintype "power_in"))
      (node (ref "X2") (pin "GND2") (pinfunction "GND1_GND2") (pintype "power_in"))
      (node (ref "X2") (pin "GND3") (pinfunction "GND2_GND3") (pintype "power_in"))
      (node (ref "X2") (pin "GND4") (pinfunction "GND3_GND4") (pintype "power_in"))
      (node (ref "Y1") (pin "2") (pinfunction "2_2") (pintype "passive"))
      (node (ref "ZZ1") (pin "P$7") (pinfunction "GND_P$7") (pintype "power_in"))
    )
    (net (code "51") (name "Net-(IC2-PB0(ICP))") (class "Default")
      (node (ref "IC2") (pin "12") (pinfunction "PB0(ICP)_12") (pintype "bidirectional"))
      (node (ref "J5") (pin "10") (pinfunction "10_10") (pintype "passive"))
    )
    (net (code "52") (name "Net-(IC2-PB1(OC1A))") (class "Default")
      (node (ref "IC2") (pin "13") (pinfunction "PB1(OC1A)_13") (pintype "bidirectional"))
      (node (ref "IC3") (pin "2") (pinfunction "I_2") (pintype "input"))
      (node (ref "J5") (pin "9") (pinfunction "9_9") (pintype "passive"))
    )
    (net (code "53") (name "Net-(IC2-PC0(ADC0))") (class "Default")
      (node (ref "IC2") (pin "23") (pinfunction "PC0(ADC0)_23") (pintype "bidirectional"))
      (node (ref "J2") (pin "1") (pinfunction "1_1") (pintype "passive"))
    )
    (net (code "54") (name "Net-(IC2-PC1(ADC1))") (class "Default")
      (node (ref "IC2") (pin "24") (pinfunction "PC1(ADC1)_24") (pintype "bidirectional"))
      (node (ref "J2") (pin "2") (pinfunction "2_2") (pintype "passive"))
    )
    (net (code "55") (name "Net-(IC2-PC2(ADC2))") (class "Default")
      (node (ref "IC2") (pin "25") (pinfunction "PC2(ADC2)_25") (pintype "bidirectional"))
      (node (ref "J2") (pin "3") (pinfunction "3_3") (pintype "passive"))
    )
    (net (code "56") (name "Net-(IC2-PC3(ADC3))") (class "Default")
      (node (ref "IC2") (pin "26") (pinfunction "PC3(ADC3)_26") (pintype "bidirectional"))
      (node (ref "J2") (pin "4") (pinfunction "4_4") (pintype "passive"))
    )
    (net (code "57") (name "Net-(IC2-PD5(T1))") (class "Default")
      (node (ref "IC2") (pin "9") (pinfunction "PD5(T1)_9") (pintype "bidirectional"))
      (node (ref "J3") (pin "6") (pinfunction "6_6") (pintype "passive"))
    )
    (net (code "58") (name "Net-(IC2-PD6(AIN0))") (class "Default")
      (node (ref "IC2") (pin "10") (pinfunction "PD6(AIN0)_10") (pintype "bidirectional"))
      (node (ref "J3") (pin "7") (pinfunction "7_7") (pintype "passive"))
    )
    (net (code "59") (name "Net-(IC2-PD7(AIN1))") (class "Default")
      (node (ref "IC2") (pin "11") (pinfunction "PD7(AIN1)_11") (pintype "bidirectional"))
      (node (ref "J3") (pin "8") (pinfunction "8_8") (pintype "passive"))
    )
    (net (code "60") (name "Net-(IC3A-O)") (class "Default")
      (node (ref "IC3") (pin "4") (pinfunction "O_4") (pintype "tri_state"))
      (node (ref "L") (pin "A") (pinfunction "A_A") (pintype "passive"))
    )
    (net (code "61") (name "Net-(IC6-*CS)") (class "Default")
      (node (ref "IC6") (pin "55") (pinfunction "*CS_55") (pintype "input"))
      (node (ref "IC6") (pin "57") (pinfunction "*WR_57") (pintype "input"))
      (node (ref "IC6") (pin "58") (pinfunction "*RD_58") (pintype "input"))
      (node (ref "R12") (pin "1") (pinfunction "1_1") (pintype "passive"))
    )
    (net (code "62") (name "Net-(IC6-RSET-BG)") (class "Default")
      (node (ref "IC6") (pin "1") (pinfunction "RSET-BG_1") (pintype "input"))
      (node (ref "R3") (pin "1") (pinfunction "1_1") (pintype "passive"))
    )
    (net (code "63") (name "Net-(R2-Pad1)") (class "Default")
      (node (ref "R2") (pin "1") (pinfunction "1_1") (pintype "passive"))
      (node (ref "R3") (pin "2") (pinfunction "2_2") (pintype "passive"))
    )
    (net (code "64") (name "Net-(RN1B-2)") (class "Default")
      (node (ref "L") (pin "C") (pinfunction "C_C") (pintype "passive"))
      (node (ref "RN1") (pin "6") (pinfunction "2_6") (pintype "passive"))
      (node (ref "RN1") (pin "7") (pinfunction "2_7") (pintype "passive"))
    )
    (net (code "65") (name "Net-(RN1D-2)") (class "Default")
      (node (ref "ON") (pin "A") (pinfunction "A_A") (pintype "passive"))
      (node (ref "RN1") (pin "5") (pinfunction "2_5") (pintype "passive"))
    )
    (net (code "66") (name "Net-(RN2B-1)") (class "Default")
      (node (ref "C4") (pin "2") (pinfunction "2_2") (pintype "passive"))
      (node (ref "RN2") (pin "1") (pinfunction "1_1") (pintype "passive"))
      (node (ref "RN2") (pin "2") (pinfunction "1_2") (pintype "passive"))
    )
    (net (code "67") (name "Net-(RN2C-1)") (class "Default")
      (node (ref "C2") (pin "2") (pinfunction "2_2") (pintype "passive"))
      (node (ref "RN2") (pin "3") (pinfunction "1_3") (pintype "passive"))
      (node (ref "RN2") (pin "4") (pinfunction "1_4") (pintype "passive"))
    )
    (net (code "68") (name "Net-(RN3A-2)") (class "Default")
      (node (ref "RN3") (pin "8") (pinfunction "2_8") (pintype "passive"))
      (node (ref "TX") (pin "A") (pinfunction "A_A") (pintype "passive"))
    )
    (net (code "69") (name "Net-(RN3B-2)") (class "Default")
      (node (ref "RN3") (pin "7") (pinfunction "2_7") (pintype "passive"))
      (node (ref "RX") (pin "A") (pinfunction "A_A") (pintype "passive"))
    )
    (net (code "70") (name "Net-(RN3C-2)") (class "Default")
      (node (ref "RN3") (pin "6") (pinfunction "2_6") (pintype "passive"))
      (node (ref "U$1") (pin "L1") (pinfunction "L1Y+_L1") (pintype "bidirectional"))
    )
    (net (code "71") (name "Net-(RN3D-2)") (class "Default")
      (node (ref "RN3") (pin "5") (pinfunction "2_5") (pintype "passive"))
      (node (ref "U$1") (pin "L3") (pinfunction "L3G+_L3") (pintype "bidirectional"))
    )
    (net (code "72") (name "Net-(ZZ1-ADJ)") (class "Default")
      (node (ref "R10") (pin "1") (pinfunction "1_1") (pintype "passive"))
      (node (ref "R8") (pin "2") (pinfunction "2_2") (pintype "passive"))
      (node (ref "ZZ1") (pin "P$9") (pinfunction "ADJ_P$9") (pintype "passive"))
    )
    (net (code "73") (name "Net-(ZZ1-CP1)") (class "Default")
      (node (ref "R9") (pin "1") (pinfunction "1_1") (pintype "passive"))
      (node (ref "ZZ1") (pin "P$5") (pinfunction "CP1_P$5") (pintype "input"))
    )
    (net (code "74") (name "Net-(ZZ1-CP2)") (class "Default")
      (node (ref "R9") (pin "2") (pinfunction "2_2") (pintype "passive"))
      (node (ref "ZZ1") (pin "P$6") (pinfunction "CP2_P$6") (pintype "input"))
    )
    (net (code "75") (name "unconnected-(IC2-ADC6-Pad19)") (class "Default")
      (node (ref "IC2") (pin "19") (pinfunction "ADC6_19") (pintype "bidirectional"))
    )
    (net (code "76") (name "unconnected-(IC2-ADC7-Pad22)") (class "Default")
      (node (ref "IC2") (pin "22") (pinfunction "ADC7_22") (pintype "bidirectional"))
    )
    (net (code "77") (name "unconnected-(IC6-NC-Pad3)") (class "Default")
      (node (ref "IC6") (pin "3") (pinfunction "NC_3") (pintype "no_connect"))
    )
    (net (code "78") (name "unconnected-(IC6-NC1-Pad60)") (class "Default")
      (node (ref "IC6") (pin "60") (pinfunction "NC1_60") (pintype "no_connect"))
    )
    (net (code "79") (name "unconnected-(IC6-NC2-Pad61)") (class "Default")
      (node (ref "IC6") (pin "61") (pinfunction "NC2_61") (pintype "no_connect"))
    )
    (net (code "80") (name "unconnected-(IC6-NC3-Pad62)") (class "Default")
      (node (ref "IC6") (pin "62") (pinfunction "NC3_62") (pintype "no_connect"))
    )
    (net (code "81") (name "unconnected-(IC6-NC4-Pad78)") (class "Default")
      (node (ref "IC6") (pin "78") (pinfunction "NC4_78") (pintype "no_connect"))
    )
    (net (code "82") (name "unconnected-(IC6-NC5-Pad79)") (class "Default")
      (node (ref "IC6") (pin "79") (pinfunction "NC5_79") (pintype "no_connect"))
    )
    (net (code "83") (name "unconnected-(IC6-NC6-Pad80)") (class "Default")
      (node (ref "IC6") (pin "80") (pinfunction "NC6_80") (pintype "no_connect"))
    )
    (net (code "84") (name "unconnected-(J1-Pad1)") (class "Default")
      (node (ref "J1") (pin "1") (pinfunction "1_1") (pintype "passive"))
    )
    (net (code "85") (name "unconnected-(J1-Pad2)") (class "Default")
      (node (ref "J1") (pin "2") (pinfunction "2_2") (pintype "passive"))
    )
    (net (code "86") (name "unconnected-(J1-Pad3)") (class "Default")
      (node (ref "J1") (pin "3") (pinfunction "3_3") (pintype "passive"))
    )
    (net (code "87") (name "unconnected-(J1-Pad4)") (class "Default")
      (node (ref "J1") (pin "4") (pinfunction "4_4") (pintype "passive"))
    )
    (net (code "88") (name "unconnected-(J1-Pad5)") (class "Default")
      (node (ref "J1") (pin "5") (pinfunction "5_5") (pintype "passive"))
    )
    (net (code "89") (name "unconnected-(J1-Pad6)") (class "Default")
      (node (ref "J1") (pin "6") (pinfunction "6_6") (pintype "passive"))
    )
    (net (code "90") (name "unconnected-(J4-Pad2)") (class "Default")
      (node (ref "J4") (pin "2") (pinfunction "2_2") (pintype "passive"))
    )
    (net (code "91") (name "unconnected-(POWER-Pad1)") (class "Default")
      (node (ref "POWER") (pin "1") (pinfunction "1_1") (pintype "passive"))
    )
    (net (code "92") (name "unconnected-(U$1-NC-PadR6)") (class "Default")
      (node (ref "U$1") (pin "R6") (pinfunction "NC_R6") (pintype "bidirectional"))
    )
    (net (code "93") (name "unconnected-(U$1-PadCH2)") (class "Default")
      (node (ref "U$1") (pin "CH2") (pinfunction "CH2_CH2") (pintype "bidirectional"))
    )
    (net (code "94") (name "unconnected-(X2-1-DAT2-Pad1)") (class "Default")
      (node (ref "X2") (pin "1") (pinfunction "1-DAT2_1") (pintype "bidirectional"))
    )
    (net (code "95") (name "unconnected-(X2-8-DAT1-Pad8)") (class "Default")
      (node (ref "X2") (pin "8") (pinfunction "8-DAT1_8") (pintype "bidirectional"))
    )
    (net (code "96") (name "unconnected-(ZZ1-IC-PadP$10)") (class "Default")
      (node (ref "ZZ1") (pin "P$10") (pinfunction "IC_P$10") (pintype "no_connect"))
    )
  )
)
